# AS5045.net
KiCad netlist of a schematic drawn in Altium Designer
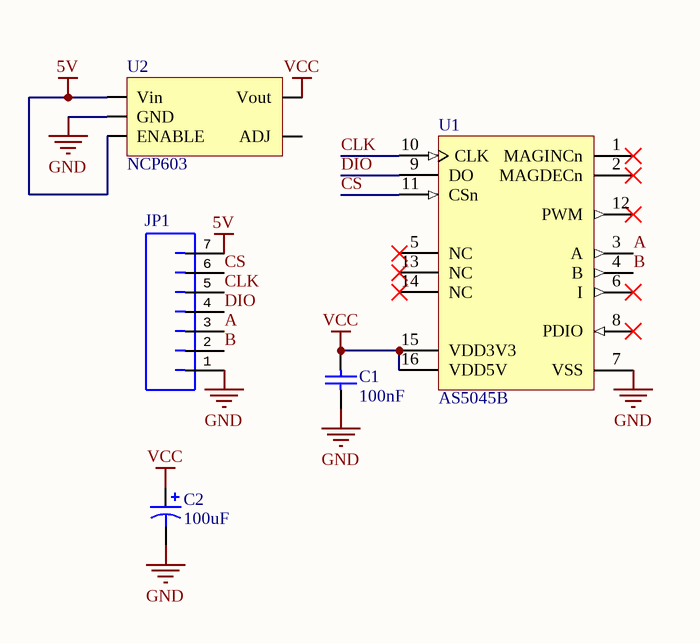
[diagram p0: AS5045.SchDoc]

(export (version "E")
  (design (tool "Eeschema 10.0.6"))
  (components
    (comp (ref "C1")
      (value "100nF")
      (footprint "CAPC0603(1608)100_M")
      (description "CAP 100nF 6.3V Â±5% 0603 (1608 Metric) Thickness 1mm SMD")
      (fields (field (name "TOLERANCE") "Â±5%"))
      (libsource (lib "Altium Content Vault") (part "CMP-1035-02575-1"))
    )
    (comp (ref "C2")
      (value "100uF")
      (footprint "AVX-CAPC7343_V")
      (libsource (lib "Components") (part "AVX-CAP-P-2"))
    )
    (comp (ref "JP1") (value "~") (footprint "JST-7-PTH") (libsource (lib "Components") (part "JST_7_RIGHT")))
    (comp (ref "U1")
      (value "AS5045B")
      (footprint "AMS-SSOP-16-6200X5300DE_L")
      (fields (field (name "MANUFACTURER") "AMS") (field (name "PARTNUMBER") "AS5045B-ASST"))
      (libsource (lib "Altium Content Vault") (part "AMS-AS5045B-SSOP-16"))
    )
    (comp (ref "U2")
      (value "NCP603")
      (footprint "SOT95P245X110-5N")
      (libsource (lib "Components") (part "NCP603"))
    )
  )
  (nets
    (net (code "1") (name "/A") (class "Default")
      (node (ref "JP1") (pin "3") (pinfunction "3_3") (pintype "passive"))
      (node (ref "U1") (pin "3") (pinfunction "A_3") (pintype "output"))
    )
    (net (code "2") (name "/B") (class "Default")
      (node (ref "JP1") (pin "2") (pinfunction "2_2") (pintype "passive"))
      (node (ref "U1") (pin "4") (pinfunction "B_4") (pintype "output"))
    )
    (net (code "3") (name "/CLK") (class "Default")
      (node (ref "JP1") (pin "5") (pinfunction "5_5") (pintype "passive"))
      (node (ref "U1") (pin "10") (pinfunction "CLK_10") (pintype "input"))
    )
    (net (code "4") (name "/CS") (class "Default")
      (node (ref "JP1") (pin "6") (pinfunction "6_6") (pintype "passive"))
      (node (ref "U1") (pin "11") (pinfunction "CSn_11") (pintype "input"))
    )
    (net (code "5") (name "/DIO") (class "Default")
      (node (ref "JP1") (pin "4") (pinfunction "4_4") (pintype "passive"))
      (node (ref "U1") (pin "9") (pinfunction "DO_9") (pintype "tri_state"))
    )
    (net (code "6") (name "5V") (class "Default")
      (node (ref "JP1") (pin "7") (pinfunction "7_7") (pintype "passive"))
      (node (ref "U2") (pin "ENABLE") (pinfunction "ENABLE_ENABLE") (pintype "passive"))
      (node (ref "U2") (pin "Vin") (pinfunction "Vin_Vin") (pintype "passive"))
    )
    (net (code "7") (name "GND") (class "Default")
      (node (ref "C1") (pin "1") (pinfunction "1_1") (pintype "passive"))
      (node (ref "C2") (pin "2") (pinfunction "2_2") (pintype "passive"))
      (node (ref "JP1") (pin "1") (pinfunction "1_1") (pintype "passive"))
      (node (ref "U1") (pin "7") (pinfunction "VSS_7") (pintype "power_in"))
      (node (ref "U2") (pin "GND") (pinfunction "GND_GND") (pintype "passive"))
    )
    (net (code "8") (name "VCC") (class "Default")
      (node (ref "C1") (pin "2") (pinfunction "2_2") (pintype "passive"))
      (node (ref "C2") (pin "1") (pinfunction "1_1") (pintype "passive"))
      (node (ref "U1") (pin "15") (pinfunction "VDD3V3_15") (pintype "power_in"))
      (node (ref "U1") (pin "16") (pinfunction "VDD5V_16") (pintype "power_in"))
      (node (ref "U2") (pin "Vout") (pinfunction "Vout_Vout") (pintype "passive"))
    )
    (net (code "9") (name "unconnected-(U1-I-Pad6)") (class "Default")
      (node (ref "U1") (pin "6") (pinfunction "I_6") (pintype "output+no_connect"))
    )
    (net (code "10") (name "unconnected-(U1-MAGDECn-Pad2)") (class "Default")
      (node (ref "U1") (pin "2") (pinfunction "MAGDECn_2") (pintype "open_collector+no_connect"))
    )
    (net (code "11") (name "unconnected-(U1-MAGINCn-Pad1)") (class "Default")
      (node (ref "U1") (pin "1") (pinfunction "MAGINCn_1") (pintype "open_collector+no_connect"))
    )
    (net (code "12") (name "unconnected-(U1-NC-Pad5)") (class "Default")
      (node (ref "U1") (pin "5") (pinfunction "NC_5") (pintype "passive+no_connect"))
    )
    (net (code "13") (name "unconnected-(U1-NC-Pad13)") (class "Default")
      (node (ref "U1") (pin "13") (pinfunction "NC_13") (pintype "passive+no_connect"))
    )
    (net (code "14") (name "unconnected-(U1-NC-Pad14)") (class "Default")
      (node (ref "U1") (pin "14") (pinfunction "NC_14") (pintype "passive+no_connect"))
    )
    (net (code "15") (name "unconnected-(U1-PDIO-Pad8)") (class "Default")
      (node (ref "U1") (pin "8") (pinfunction "PDIO_8") (pintype "input+no_connect"))
    )
    (net (code "16") (name "unconnected-(U1-PWM-Pad12)") (class "Default")
      (node (ref "U1") (pin "12") (pinfunction "PWM_12") (pintype "output+no_connect"))
    )
    (net (code "17") (name "unconnected-(U2-PadADJ)") (class "Default")
      (node (ref "U2") (pin "ADJ") (pinfunction "ADJ_ADJ") (pintype "passive"))
    )
  )
)
